# SchematicsEASYEDA.net
KiCad netlist of a schematic drawn in EasyEDA
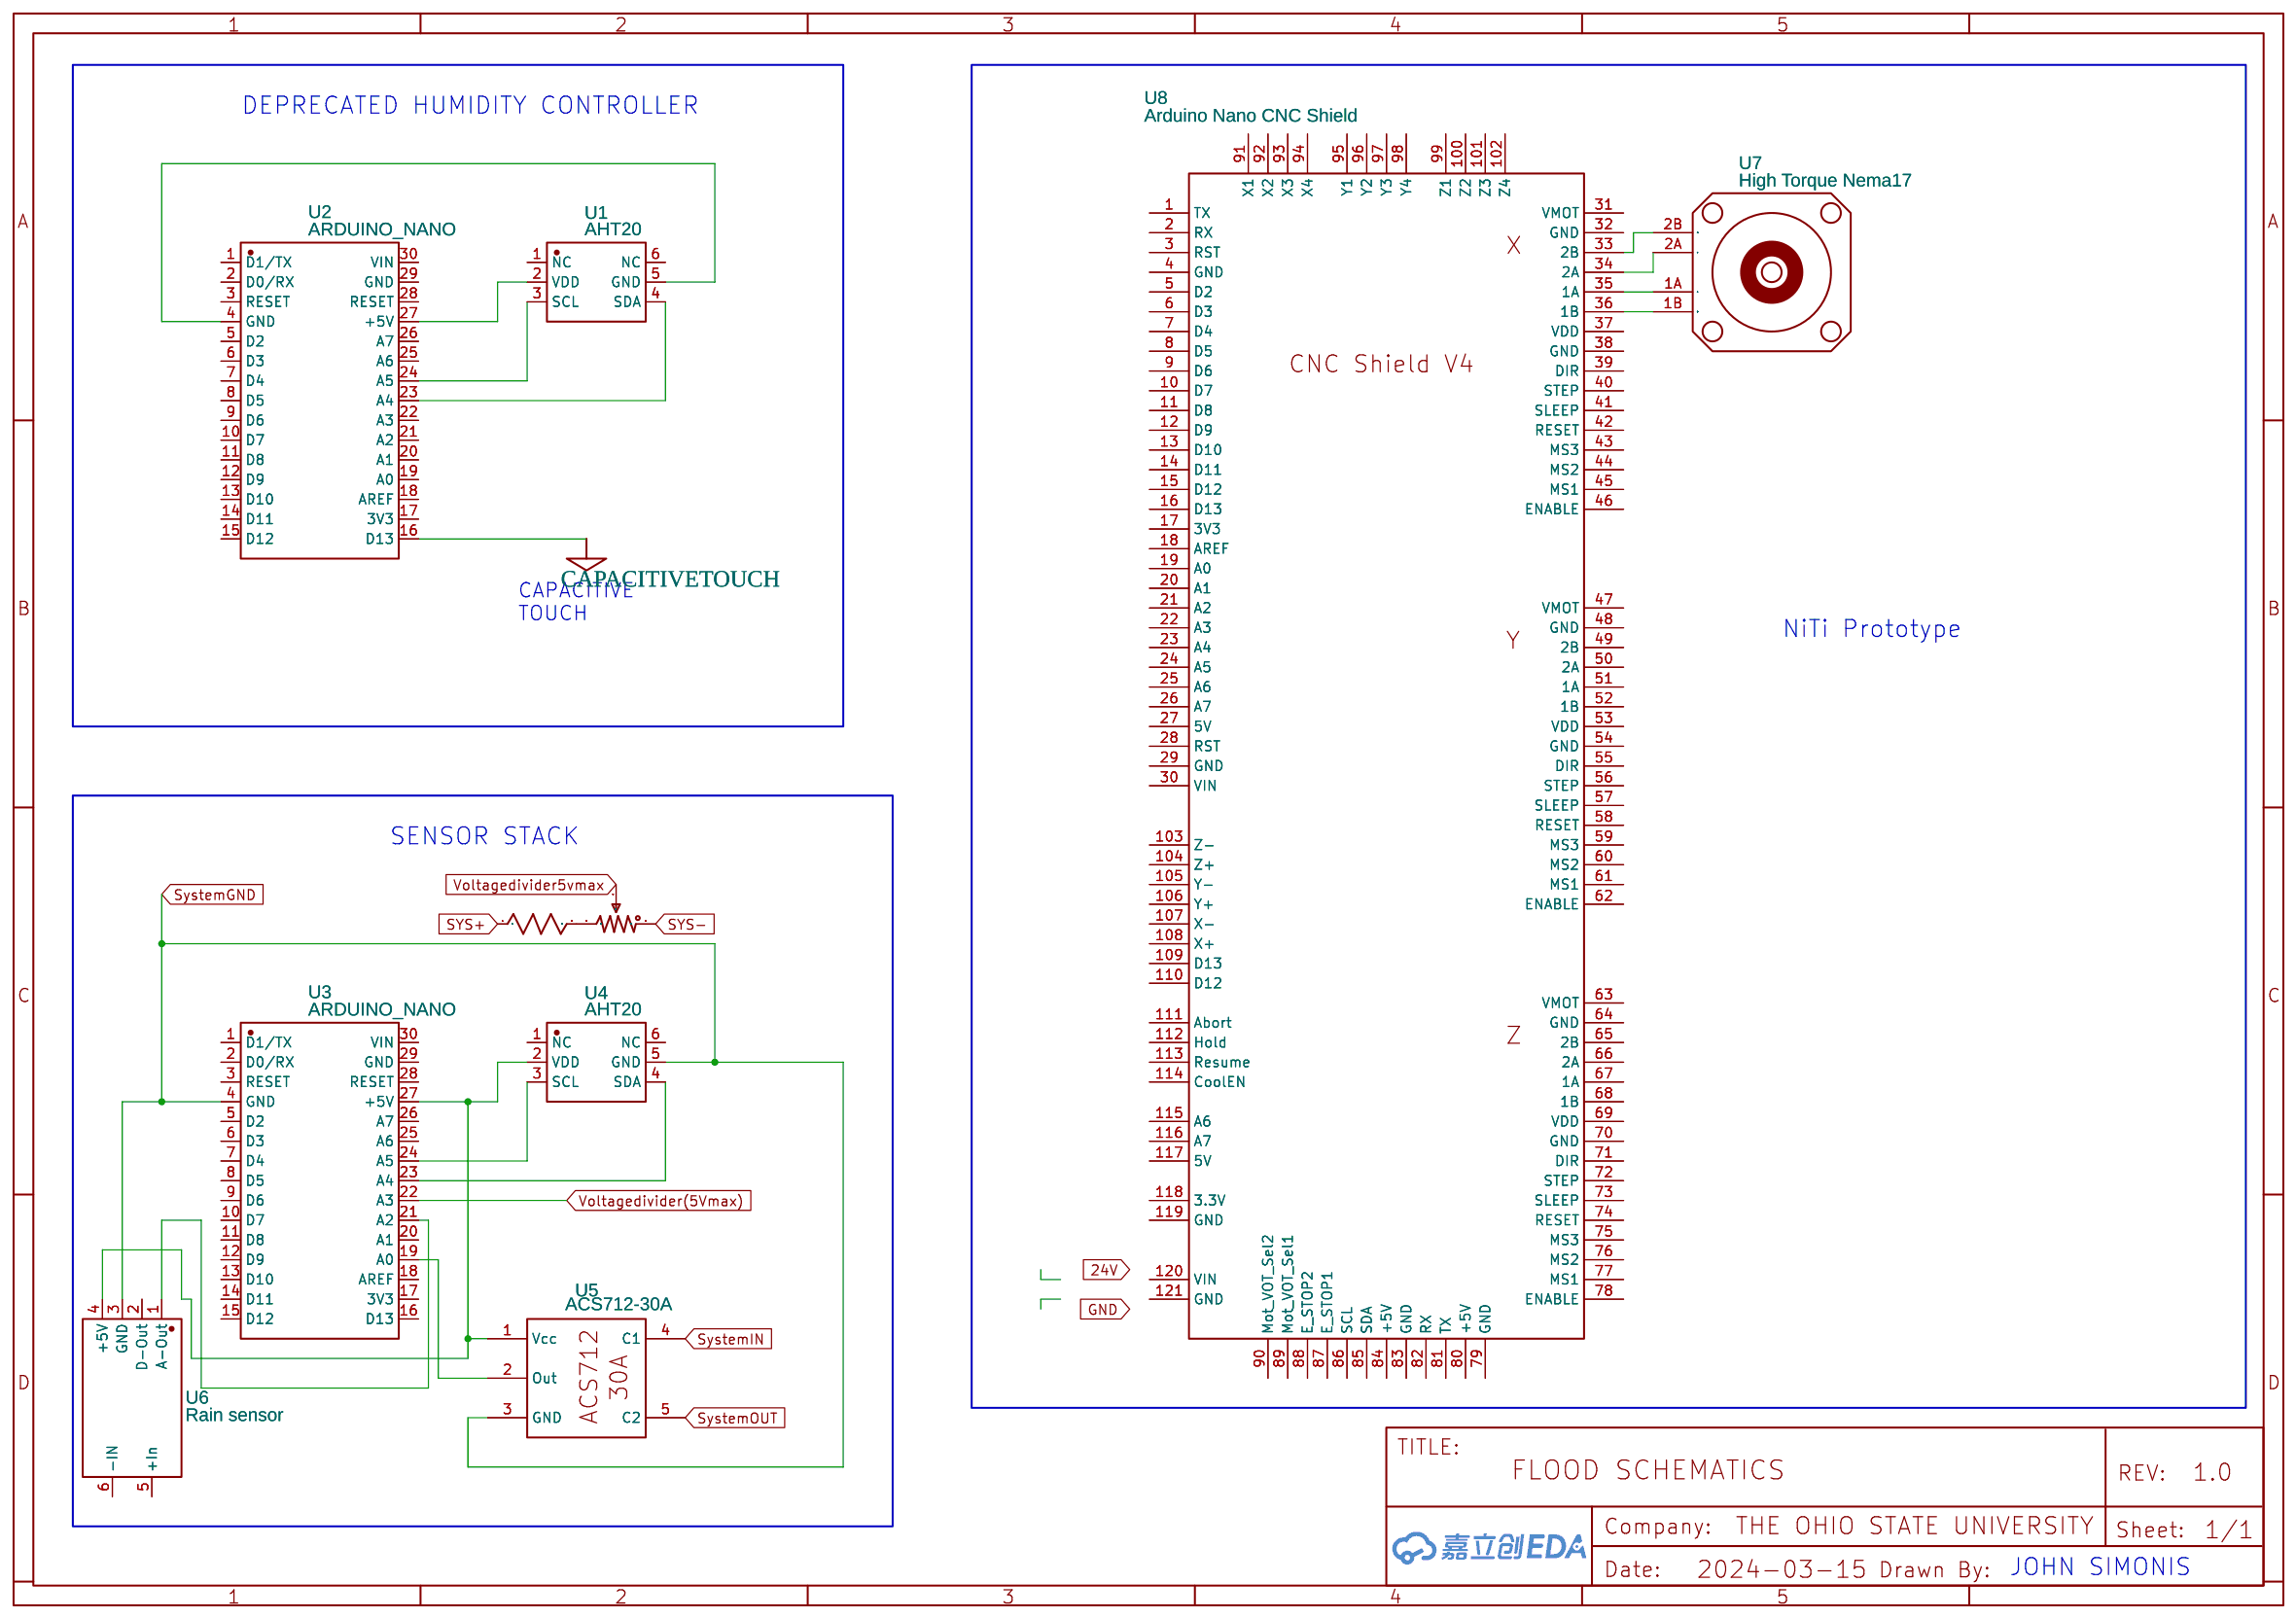
[diagram p0: schematic sheet]

(export (version "E")
  (design (tool "Eeschema 10.0.6"))
  (components
    (comp (ref "R1") (value "1k") (libsource (lib "") (part "R_0603_US")))
    (comp (ref "RP1") (value "R_3386P_US") (libsource (lib "") (part "R_3386P_US")))
    (comp (ref "U1")
      (value "AHT20")
      (fields (field (name "Manufacturer") "广州奥松"))
      (libsource (lib "") (part "AHT20"))
    )
    (comp (ref "U2") (value "ARDUINO_NANO") (libsource (lib "") (part "ARDUINO_NANO")))
    (comp (ref "U3") (value "ARDUINO_NANO") (libsource (lib "") (part "ARDUINO_NANO")))
    (comp (ref "U4")
      (value "AHT20")
      (fields (field (name "Manufacturer") "广州奥松"))
      (libsource (lib "") (part "AHT20"))
    )
    (comp (ref "U5") (value "ACS712-30A") (libsource (lib "") (part "ACS712-30A")))
    (comp (ref "U6") (value "Rain sensor") (libsource (lib "") (part "Rain sensor")))
    (comp (ref "U7") (value "High Torque Nema17") (libsource (lib "") (part "Nema17")))
    (comp (ref "U8") (value "Arduino Nano CNC Shield") (libsource (lib "") (part "Arduino Nano CNC Shield")))
  )
  (nets
    (net (code "2") (name "CAPACITIVETOUCH") (class "Default")
      (node (ref "U2") (pin "16") (pinfunction "D13_16") (pintype "unspecified"))
    )
    (net (code "4") (name "Net-(R1-Pad2)") (class "Default")
      (node (ref "R1") (pin "2") (pinfunction "2_2") (pintype "unspecified"))
      (node (ref "RP1") (pin "3") (pinfunction "3_3") (pintype "unspecified"))
    )
    (net (code "5") (name "Net-(U1-GND)") (class "Default")
      (node (ref "U1") (pin "5") (pinfunction "GND_5") (pintype "unspecified"))
      (node (ref "U2") (pin "4") (pinfunction "GND_4") (pintype "unspecified"))
    )
    (net (code "6") (name "Net-(U1-SCL)") (class "Default")
      (node (ref "U1") (pin "3") (pinfunction "SCL_3") (pintype "unspecified"))
      (node (ref "U2") (pin "24") (pinfunction "A5_24") (pintype "unspecified"))
    )
    (net (code "7") (name "Net-(U1-SDA)") (class "Default")
      (node (ref "U1") (pin "4") (pinfunction "SDA_4") (pintype "unspecified"))
      (node (ref "U2") (pin "23") (pinfunction "A4_23") (pintype "unspecified"))
    )
    (net (code "8") (name "Net-(U1-VDD)") (class "Default")
      (node (ref "U1") (pin "2") (pinfunction "VDD_2") (pintype "unspecified"))
      (node (ref "U2") (pin "27") (pinfunction "+5V_27") (pintype "unspecified"))
    )
    (net (code "9") (name "Net-(U3-+5V)") (class "Default")
      (node (ref "U3") (pin "27") (pinfunction "+5V_27") (pintype "unspecified"))
      (node (ref "U4") (pin "2") (pinfunction "VDD_2") (pintype "unspecified"))
      (node (ref "U5") (pin "1") (pinfunction "Vcc_1") (pintype "unspecified"))
      (node (ref "U6") (pin "4") (pinfunction "+5V_4") (pintype "unspecified"))
    )
    (net (code "10") (name "Net-(U3-A0)") (class "Default")
      (node (ref "U3") (pin "19") (pinfunction "A0_19") (pintype "unspecified"))
      (node (ref "U5") (pin "2") (pinfunction "Out_2") (pintype "unspecified"))
    )
    (net (code "11") (name "Net-(U3-A2)") (class "Default")
      (node (ref "U3") (pin "21") (pinfunction "A2_21") (pintype "unspecified"))
      (node (ref "U6") (pin "1") (pinfunction "A-Out_1") (pintype "unspecified"))
    )
    (net (code "12") (name "Net-(U3-A4)") (class "Default")
      (node (ref "U3") (pin "23") (pinfunction "A4_23") (pintype "unspecified"))
      (node (ref "U4") (pin "4") (pinfunction "SDA_4") (pintype "unspecified"))
    )
    (net (code "13") (name "Net-(U3-A5)") (class "Default")
      (node (ref "U3") (pin "24") (pinfunction "A5_24") (pintype "unspecified"))
      (node (ref "U4") (pin "3") (pinfunction "SCL_3") (pintype "unspecified"))
    )
    (net (code "14") (name "Net-(U7-A-Pad1A)") (class "Default")
      (node (ref "U7") (pin "1A") (pinfunction "A_1A") (pintype "unspecified"))
      (node (ref "U8") (pin "35") (pinfunction "1A_35") (pintype "unspecified"))
    )
    (net (code "15") (name "Net-(U7-A-Pad2A)") (class "Default")
      (node (ref "U7") (pin "2A") (pinfunction "A_2A") (pintype "unspecified"))
      (node (ref "U8") (pin "34") (pinfunction "2A_34") (pintype "unspecified"))
    )
    (net (code "16") (name "Net-(U7-B-Pad1B)") (class "Default")
      (node (ref "U7") (pin "1B") (pinfunction "B_1B") (pintype "unspecified"))
      (node (ref "U8") (pin "36") (pinfunction "1B_36") (pintype "unspecified"))
    )
    (net (code "17") (name "Net-(U7-B-Pad2B)") (class "Default")
      (node (ref "U7") (pin "2B") (pinfunction "B_2B") (pintype "unspecified"))
      (node (ref "U8") (pin "33") (pinfunction "2B_33") (pintype "unspecified"))
    )
    (net (code "18") (name "SYS+") (class "Default")
      (node (ref "R1") (pin "1") (pinfunction "1_1") (pintype "unspecified"))
    )
    (net (code "19") (name "SYS-") (class "Default")
      (node (ref "RP1") (pin "1") (pinfunction "1_1") (pintype "unspecified"))
    )
    (net (code "20") (name "SystemGND") (class "Default")
      (node (ref "U3") (pin "4") (pinfunction "GND_4") (pintype "unspecified"))
      (node (ref "U4") (pin "5") (pinfunction "GND_5") (pintype "unspecified"))
      (node (ref "U5") (pin "3") (pinfunction "GND_3") (pintype "unspecified"))
      (node (ref "U6") (pin "3") (pinfunction "GND_3") (pintype "unspecified"))
    )
    (net (code "21") (name "SystemIN") (class "Default")
      (node (ref "U5") (pin "4") (pinfunction "C1_4") (pintype "unspecified"))
    )
    (net (code "22") (name "SystemOUT") (class "Default")
      (node (ref "U5") (pin "5") (pinfunction "C2_5") (pintype "unspecified"))
    )
    (net (code "23") (name "Voltagedivider(5Vmax)") (class "Default")
      (node (ref "U3") (pin "22") (pinfunction "A3_22") (pintype "unspecified"))
    )
    (net (code "24") (name "Voltagedivider5vmax") (class "Default")
      (node (ref "RP1") (pin "2") (pinfunction "2_2") (pintype "unspecified"))
    )
    (net (code "25") (name "unconnected-(U1-NC-Pad1)") (class "Default")
      (node (ref "U1") (pin "1") (pinfunction "NC_1") (pintype "unspecified"))
    )
    (net (code "26") (name "unconnected-(U1-NC-Pad6)") (class "Default")
      (node (ref "U1") (pin "6") (pinfunction "NC_6") (pintype "unspecified"))
    )
    (net (code "27") (name "unconnected-(U2-3V3-Pad17)") (class "Default")
      (node (ref "U2") (pin "17") (pinfunction "3V3_17") (pintype "unspecified"))
    )
    (net (code "28") (name "unconnected-(U2-A0-Pad19)") (class "Default")
      (node (ref "U2") (pin "19") (pinfunction "A0_19") (pintype "unspecified"))
    )
    (net (code "29") (name "unconnected-(U2-A1-Pad20)") (class "Default")
      (node (ref "U2") (pin "20") (pinfunction "A1_20") (pintype "unspecified"))
    )
    (net (code "30") (name "unconnected-(U2-A2-Pad21)") (class "Default")
      (node (ref "U2") (pin "21") (pinfunction "A2_21") (pintype "unspecified"))
    )
    (net (code "31") (name "unconnected-(U2-A3-Pad22)") (class "Default")
      (node (ref "U2") (pin "22") (pinfunction "A3_22") (pintype "unspecified"))
    )
    (net (code "32") (name "unconnected-(U2-A6-Pad25)") (class "Default")
      (node (ref "U2") (pin "25") (pinfunction "A6_25") (pintype "unspecified"))
    )
    (net (code "33") (name "unconnected-(U2-A7-Pad26)") (class "Default")
      (node (ref "U2") (pin "26") (pinfunction "A7_26") (pintype "unspecified"))
    )
    (net (code "34") (name "unconnected-(U2-AREF-Pad18)") (class "Default")
      (node (ref "U2") (pin "18") (pinfunction "AREF_18") (pintype "unspecified"))
    )
    (net (code "35") (name "unconnected-(U2-D0{slash}RX-Pad2)") (class "Default")
      (node (ref "U2") (pin "2") (pinfunction "D0/RX_2") (pintype "unspecified"))
    )
    (net (code "36") (name "unconnected-(U2-D1{slash}TX-Pad1)") (class "Default")
      (node (ref "U2") (pin "1") (pinfunction "D1/TX_1") (pintype "unspecified"))
    )
    (net (code "37") (name "unconnected-(U2-D2-Pad5)") (class "Default")
      (node (ref "U2") (pin "5") (pinfunction "D2_5") (pintype "unspecified"))
    )
    (net (code "38") (name "unconnected-(U2-D3-Pad6)") (class "Default")
      (node (ref "U2") (pin "6") (pinfunction "D3_6") (pintype "unspecified"))
    )
    (net (code "39") (name "unconnected-(U2-D4-Pad7)") (class "Default")
      (node (ref "U2") (pin "7") (pinfunction "D4_7") (pintype "unspecified"))
    )
    (net (code "40") (name "unconnected-(U2-D5-Pad8)") (class "Default")
      (node (ref "U2") (pin "8") (pinfunction "D5_8") (pintype "unspecified"))
    )
    (net (code "41") (name "unconnected-(U2-D6-Pad9)") (class "Default")
      (node (ref "U2") (pin "9") (pinfunction "D6_9") (pintype "unspecified"))
    )
    (net (code "42") (name "unconnected-(U2-D7-Pad10)") (class "Default")
      (node (ref "U2") (pin "10") (pinfunction "D7_10") (pintype "unspecified"))
    )
    (net (code "43") (name "unconnected-(U2-D8-Pad11)") (class "Default")
      (node (ref "U2") (pin "11") (pinfunction "D8_11") (pintype "unspecified"))
    )
    (net (code "44") (name "unconnected-(U2-D9-Pad12)") (class "Default")
      (node (ref "U2") (pin "12") (pinfunction "D9_12") (pintype "unspecified"))
    )
    (net (code "45") (name "unconnected-(U2-D10-Pad13)") (class "Default")
      (node (ref "U2") (pin "13") (pinfunction "D10_13") (pintype "unspecified"))
    )
    (net (code "46") (name "unconnected-(U2-D11-Pad14)") (class "Default")
      (node (ref "U2") (pin "14") (pinfunction "D11_14") (pintype "unspecified"))
    )
    (net (code "47") (name "unconnected-(U2-D12-Pad15)") (class "Default")
      (node (ref "U2") (pin "15") (pinfunction "D12_15") (pintype "unspecified"))
    )
    (net (code "48") (name "unconnected-(U2-GND-Pad29)") (class "Default")
      (node (ref "U2") (pin "29") (pinfunction "GND_29") (pintype "unspecified"))
    )
    (net (code "49") (name "unconnected-(U2-RESET-Pad3)") (class "Default")
      (node (ref "U2") (pin "3") (pinfunction "RESET_3") (pintype "unspecified"))
    )
    (net (code "50") (name "unconnected-(U2-RESET-Pad28)") (class "Default")
      (node (ref "U2") (pin "28") (pinfunction "RESET_28") (pintype "unspecified"))
    )
    (net (code "51") (name "unconnected-(U2-VIN-Pad30)") (class "Default")
      (node (ref "U2") (pin "30") (pinfunction "VIN_30") (pintype "unspecified"))
    )
    (net (code "52") (name "unconnected-(U3-3V3-Pad17)") (class "Default")
      (node (ref "U3") (pin "17") (pinfunction "3V3_17") (pintype "unspecified"))
    )
    (net (code "53") (name "unconnected-(U3-A1-Pad20)") (class "Default")
      (node (ref "U3") (pin "20") (pinfunction "A1_20") (pintype "unspecified"))
    )
    (net (code "54") (name "unconnected-(U3-A6-Pad25)") (class "Default")
      (node (ref "U3") (pin "25") (pinfunction "A6_25") (pintype "unspecified"))
    )
    (net (code "55") (name "unconnected-(U3-A7-Pad26)") (class "Default")
      (node (ref "U3") (pin "26") (pinfunction "A7_26") (pintype "unspecified"))
    )
    (net (code "56") (name "unconnected-(U3-AREF-Pad18)") (class "Default")
      (node (ref "U3") (pin "18") (pinfunction "AREF_18") (pintype "unspecified"))
    )
    (net (code "57") (name "unconnected-(U3-D0{slash}RX-Pad2)") (class "Default")
      (node (ref "U3") (pin "2") (pinfunction "D0/RX_2") (pintype "unspecified"))
    )
    (net (code "58") (name "unconnected-(U3-D1{slash}TX-Pad1)") (class "Default")
      (node (ref "U3") (pin "1") (pinfunction "D1/TX_1") (pintype "unspecified"))
    )
    (net (code "59") (name "unconnected-(U3-D2-Pad5)") (class "Default")
      (node (ref "U3") (pin "5") (pinfunction "D2_5") (pintype "unspecified"))
    )
    (net (code "60") (name "unconnected-(U3-D3-Pad6)") (class "Default")
      (node (ref "U3") (pin "6") (pinfunction "D3_6") (pintype "unspecified"))
    )
    (net (code "61") (name "unconnected-(U3-D4-Pad7)") (class "Default")
      (node (ref "U3") (pin "7") (pinfunction "D4_7") (pintype "unspecified"))
    )
    (net (code "62") (name "unconnected-(U3-D5-Pad8)") (class "Default")
      (node (ref "U3") (pin "8") (pinfunction "D5_8") (pintype "unspecified"))
    )
    (net (code "63") (name "unconnected-(U3-D6-Pad9)") (class "Default")
      (node (ref "U3") (pin "9") (pinfunction "D6_9") (pintype "unspecified"))
    )
    (net (code "64") (name "unconnected-(U3-D7-Pad10)") (class "Default")
      (node (ref "U3") (pin "10") (pinfunction "D7_10") (pintype "unspecified"))
    )
    (net (code "65") (name "unconnected-(U3-D8-Pad11)") (class "Default")
      (node (ref "U3") (pin "11") (pinfunction "D8_11") (pintype "unspecified"))
    )
    (net (code "66") (name "unconnected-(U3-D9-Pad12)") (class "Default")
      (node (ref "U3") (pin "12") (pinfunction "D9_12") (pintype "unspecified"))
    )
    (net (code "67") (name "unconnected-(U3-D10-Pad13)") (class "Default")
      (node (ref "U3") (pin "13") (pinfunction "D10_13") (pintype "unspecified"))
    )
    (net (code "68") (name "unconnected-(U3-D11-Pad14)") (class "Default")
      (node (ref "U3") (pin "14") (pinfunction "D11_14") (pintype "unspecified"))
    )
    (net (code "69") (name "unconnected-(U3-D12-Pad15)") (class "Default")
      (node (ref "U3") (pin "15") (pinfunction "D12_15") (pintype "unspecified"))
    )
    (net (code "70") (name "unconnected-(U3-D13-Pad16)") (class "Default")
      (node (ref "U3") (pin "16") (pinfunction "D13_16") (pintype "unspecified"))
    )
    (net (code "71") (name "unconnected-(U3-GND-Pad29)") (class "Default")
      (node (ref "U3") (pin "29") (pinfunction "GND_29") (pintype "unspecified"))
    )
    (net (code "72") (name "unconnected-(U3-RESET-Pad3)") (class "Default")
      (node (ref "U3") (pin "3") (pinfunction "RESET_3") (pintype "unspecified"))
    )
    (net (code "73") (name "unconnected-(U3-RESET-Pad28)") (class "Default")
      (node (ref "U3") (pin "28") (pinfunction "RESET_28") (pintype "unspecified"))
    )
    (net (code "74") (name "unconnected-(U3-VIN-Pad30)") (class "Default")
      (node (ref "U3") (pin "30") (pinfunction "VIN_30") (pintype "unspecified"))
    )
    (net (code "75") (name "unconnected-(U4-NC-Pad1)") (class "Default")
      (node (ref "U4") (pin "1") (pinfunction "NC_1") (pintype "unspecified"))
    )
    (net (code "76") (name "unconnected-(U4-NC-Pad6)") (class "Default")
      (node (ref "U4") (pin "6") (pinfunction "NC_6") (pintype "unspecified"))
    )
    (net (code "77") (name "unconnected-(U6-+In-Pad5)") (class "Default")
      (node (ref "U6") (pin "5") (pinfunction "+In_5") (pintype "unspecified"))
    )
    (net (code "78") (name "unconnected-(U6--IN-Pad6)") (class "Default")
      (node (ref "U6") (pin "6") (pinfunction "-IN_6") (pintype "unspecified"))
    )
    (net (code "79") (name "unconnected-(U6-D-Out-Pad2)") (class "Default")
      (node (ref "U6") (pin "2") (pinfunction "D-Out_2") (pintype "unspecified"))
    )
    (net (code "80") (name "unconnected-(U8-+5V-Pad80)") (class "Default")
      (node (ref "U8") (pin "80") (pinfunction "+5V_80") (pintype "unspecified"))
    )
    (net (code "81") (name "unconnected-(U8-+5V-Pad84)") (class "Default")
      (node (ref "U8") (pin "84") (pinfunction "+5V_84") (pintype "unspecified"))
    )
    (net (code "82") (name "unconnected-(U8-1A-Pad51)") (class "Default")
      (node (ref "U8") (pin "51") (pinfunction "1A_51") (pintype "unspecified"))
    )
    (net (code "83") (name "unconnected-(U8-1A-Pad67)") (class "Default")
      (node (ref "U8") (pin "67") (pinfunction "1A_67") (pintype "unspecified"))
    )
    (net (code "84") (name "unconnected-(U8-1B-Pad52)") (class "Default")
      (node (ref "U8") (pin "52") (pinfunction "1B_52") (pintype "unspecified"))
    )
    (net (code "85") (name "unconnected-(U8-1B-Pad68)") (class "Default")
      (node (ref "U8") (pin "68") (pinfunction "1B_68") (pintype "unspecified"))
    )
    (net (code "86") (name "unconnected-(U8-2A-Pad50)") (class "Default")
      (node (ref "U8") (pin "50") (pinfunction "2A_50") (pintype "unspecified"))
    )
    (net (code "87") (name "unconnected-(U8-2A-Pad66)") (class "Default")
      (node (ref "U8") (pin "66") (pinfunction "2A_66") (pintype "unspecified"))
    )
    (net (code "88") (name "unconnected-(U8-2B-Pad49)") (class "Default")
      (node (ref "U8") (pin "49") (pinfunction "2B_49") (pintype "unspecified"))
    )
    (net (code "89") (name "unconnected-(U8-2B-Pad65)") (class "Default")
      (node (ref "U8") (pin "65") (pinfunction "2B_65") (pintype "unspecified"))
    )
    (net (code "90") (name "unconnected-(U8-3.3V-Pad118)") (class "Default")
      (node (ref "U8") (pin "118") (pinfunction "3.3V_118") (pintype "unspecified"))
    )
    (net (code "91") (name "unconnected-(U8-3V3-Pad17)") (class "Default")
      (node (ref "U8") (pin "17") (pinfunction "3V3_17") (pintype "unspecified"))
    )
    (net (code "92") (name "unconnected-(U8-5V-Pad27)") (class "Default")
      (node (ref "U8") (pin "27") (pinfunction "5V_27") (pintype "unspecified"))
    )
    (net (code "93") (name "unconnected-(U8-5V-Pad117)") (class "Default")
      (node (ref "U8") (pin "117") (pinfunction "5V_117") (pintype "unspecified"))
    )
    (net (code "94") (name "unconnected-(U8-A0-Pad19)") (class "Default")
      (node (ref "U8") (pin "19") (pinfunction "A0_19") (pintype "unspecified"))
    )
    (net (code "95") (name "unconnected-(U8-A1-Pad20)") (class "Default")
      (node (ref "U8") (pin "20") (pinfunction "A1_20") (pintype "unspecified"))
    )
    (net (code "96") (name "unconnected-(U8-A2-Pad21)") (class "Default")
      (node (ref "U8") (pin "21") (pinfunction "A2_21") (pintype "unspecified"))
    )
    (net (code "97") (name "unconnected-(U8-A3-Pad22)") (class "Default")
      (node (ref "U8") (pin "22") (pinfunction "A3_22") (pintype "unspecified"))
    )
    (net (code "98") (name "unconnected-(U8-A4-Pad23)") (class "Default")
      (node (ref "U8") (pin "23") (pinfunction "A4_23") (pintype "unspecified"))
    )
    (net (code "99") (name "unconnected-(U8-A5-Pad24)") (class "Default")
      (node (ref "U8") (pin "24") (pinfunction "A5_24") (pintype "unspecified"))
    )
    (net (code "100") (name "unconnected-(U8-A6-Pad25)") (class "Default")
      (node (ref "U8") (pin "25") (pinfunction "A6_25") (pintype "unspecified"))
    )
    (net (code "101") (name "unconnected-(U8-A6-Pad115)") (class "Default")
      (node (ref "U8") (pin "115") (pinfunction "A6_115") (pintype "unspecified"))
    )
    (net (code "102") (name "unconnected-(U8-A7-Pad26)") (class "Default")
      (node (ref "U8") (pin "26") (pinfunction "A7_26") (pintype "unspecified"))
    )
    (net (code "103") (name "unconnected-(U8-A7-Pad116)") (class "Default")
      (node (ref "U8") (pin "116") (pinfunction "A7_116") (pintype "unspecified"))
    )
    (net (code "104") (name "unconnected-(U8-AREF-Pad18)") (class "Default")
      (node (ref "U8") (pin "18") (pinfunction "AREF_18") (pintype "unspecified"))
    )
    (net (code "105") (name "unconnected-(U8-Abort-Pad111)") (class "Default")
      (node (ref "U8") (pin "111") (pinfunction "Abort_111") (pintype "unspecified"))
    )
    (net (code "106") (name "unconnected-(U8-CoolEN-Pad114)") (class "Default")
      (node (ref "U8") (pin "114") (pinfunction "CoolEN_114") (pintype "unspecified"))
    )
    (net (code "107") (name "unconnected-(U8-D2-Pad5)") (class "Default")
      (node (ref "U8") (pin "5") (pinfunction "D2_5") (pintype "unspecified"))
    )
    (net (code "108") (name "unconnected-(U8-D3-Pad6)") (class "Default")
      (node (ref "U8") (pin "6") (pinfunction "D3_6") (pintype "unspecified"))
    )
    (net (code "109") (name "unconnected-(U8-D4-Pad7)") (class "Default")
      (node (ref "U8") (pin "7") (pinfunction "D4_7") (pintype "unspecified"))
    )
    (net (code "110") (name "unconnected-(U8-D5-Pad8)") (class "Default")
      (node (ref "U8") (pin "8") (pinfunction "D5_8") (pintype "unspecified"))
    )
    (net (code "111") (name "unconnected-(U8-D6-Pad9)") (class "Default")
      (node (ref "U8") (pin "9") (pinfunction "D6_9") (pintype "unspecified"))
    )
    (net (code "112") (name "unconnected-(U8-D7-Pad10)") (class "Default")
      (node (ref "U8") (pin "10") (pinfunction "D7_10") (pintype "unspecified"))
    )
    (net (code "113") (name "unconnected-(U8-D8-Pad11)") (class "Default")
      (node (ref "U8") (pin "11") (pinfunction "D8_11") (pintype "unspecified"))
    )
    (net (code "114") (name "unconnected-(U8-D9-Pad12)") (class "Default")
      (node (ref "U8") (pin "12") (pinfunction "D9_12") (pintype "unspecified"))
    )
    (net (code "115") (name "unconnected-(U8-D10-Pad13)") (class "Default")
      (node (ref "U8") (pin "13") (pinfunction "D10_13") (pintype "unspecified"))
    )
    (net (code "116") (name "unconnected-(U8-D11-Pad14)") (class "Default")
      (node (ref "U8") (pin "14") (pinfunction "D11_14") (pintype "unspecified"))
    )
    (net (code "117") (name "unconnected-(U8-D12-Pad15)") (class "Default")
      (node (ref "U8") (pin "15") (pinfunction "D12_15") (pintype "unspecified"))
    )
    (net (code "118") (name "unconnected-(U8-D12-Pad110)") (class "Default")
      (node (ref "U8") (pin "110") (pinfunction "D12_110") (pintype "unspecified"))
    )
    (net (code "119") (name "unconnected-(U8-D13-Pad16)") (class "Default")
      (node (ref "U8") (pin "16") (pinfunction "D13_16") (pintype "unspecified"))
    )
    (net (code "120") (name "unconnected-(U8-D13-Pad109)") (class "Default")
      (node (ref "U8") (pin "109") (pinfunction "D13_109") (pintype "unspecified"))
    )
    (net (code "121") (name "unconnected-(U8-DIR-Pad39)") (class "Default")
      (node (ref "U8") (pin "39") (pinfunction "DIR_39") (pintype "unspecified"))
    )
    (net (code "122") (name "unconnected-(U8-DIR-Pad55)") (class "Default")
      (node (ref "U8") (pin "55") (pinfunction "DIR_55") (pintype "unspecified"))
    )
    (net (code "123") (name "unconnected-(U8-DIR-Pad71)") (class "Default")
      (node (ref "U8") (pin "71") (pinfunction "DIR_71") (pintype "unspecified"))
    )
    (net (code "124") (name "unconnected-(U8-ENABLE-Pad46)") (class "Default")
      (node (ref "U8") (pin "46") (pinfunction "ENABLE_46") (pintype "unspecified"))
    )
    (net (code "125") (name "unconnected-(U8-ENABLE-Pad62)") (class "Default")
      (node (ref "U8") (pin "62") (pinfunction "ENABLE_62") (pintype "unspecified"))
    )
    (net (code "126") (name "unconnected-(U8-ENABLE-Pad78)") (class "Default")
      (node (ref "U8") (pin "78") (pinfunction "ENABLE_78") (pintype "unspecified"))
    )
    (net (code "127") (name "unconnected-(U8-E_STOP1-Pad87)") (class "Default")
      (node (ref "U8") (pin "87") (pinfunction "E_STOP1_87") (pintype "unspecified"))
    )
    (net (code "128") (name "unconnected-(U8-E_STOP2-Pad88)") (class "Default")
      (node (ref "U8") (pin "88") (pinfunction "E_STOP2_88") (pintype "unspecified"))
    )
    (net (code "129") (name "unconnected-(U8-GND-Pad4)") (class "Default")
      (node (ref "U8") (pin "4") (pinfunction "GND_4") (pintype "unspecified"))
    )
    (net (code "130") (name "unconnected-(U8-GND-Pad29)") (class "Default")
      (node (ref "U8") (pin "29") (pinfunction "GND_29") (pintype "unspecified"))
    )
    (net (code "131") (name "unconnected-(U8-GND-Pad32)") (class "Default")
      (node (ref "U8") (pin "32") (pinfunction "GND_32") (pintype "unspecified"))
    )
    (net (code "132") (name "unconnected-(U8-GND-Pad38)") (class "Default")
      (node (ref "U8") (pin "38") (pinfunction "GND_38") (pintype "unspecified"))
    )
    (net (code "133") (name "unconnected-(U8-GND-Pad48)") (class "Default")
      (node (ref "U8") (pin "48") (pinfunction "GND_48") (pintype "unspecified"))
    )
    (net (code "134") (name "unconnected-(U8-GND-Pad54)") (class "Default")
      (node (ref "U8") (pin "54") (pinfunction "GND_54") (pintype "unspecified"))
    )
    (net (code "135") (name "unconnected-(U8-GND-Pad64)") (class "Default")
      (node (ref "U8") (pin "64") (pinfunction "GND_64") (pintype "unspecified"))
    )
    (net (code "136") (name "unconnected-(U8-GND-Pad70)") (class "Default")
      (node (ref "U8") (pin "70") (pinfunction "GND_70") (pintype "unspecified"))
    )
    (net (code "137") (name "unconnected-(U8-GND-Pad79)") (class "Default")
      (node (ref "U8") (pin "79") (pinfunction "GND_79") (pintype "unspecified"))
    )
    (net (code "138") (name "unconnected-(U8-GND-Pad83)") (class "Default")
      (node (ref "U8") (pin "83") (pinfunction "GND_83") (pintype "unspecified"))
    )
    (net (code "139") (name "unconnected-(U8-GND-Pad119)") (class "Default")
      (node (ref "U8") (pin "119") (pinfunction "GND_119") (pintype "unspecified"))
    )
    (net (code "140") (name "unconnected-(U8-GND-Pad121)") (class "Default")
      (node (ref "U8") (pin "121") (pinfunction "GND_121") (pintype "unspecified"))
    )
    (net (code "141") (name "unconnected-(U8-Hold-Pad112)") (class "Default")
      (node (ref "U8") (pin "112") (pinfunction "Hold_112") (pintype "unspecified"))
    )
    (net (code "142") (name "unconnected-(U8-MS1-Pad45)") (class "Default")
      (node (ref "U8") (pin "45") (pinfunction "MS1_45") (pintype "unspecified"))
    )
    (net (code "143") (name "unconnected-(U8-MS1-Pad61)") (class "Default")
      (node (ref "U8") (pin "61") (pinfunction "MS1_61") (pintype "unspecified"))
    )
    (net (code "144") (name "unconnected-(U8-MS1-Pad77)") (class "Default")
      (node (ref "U8") (pin "77") (pinfunction "MS1_77") (pintype "unspecified"))
    )
    (net (code "145") (name "unconnected-(U8-MS2-Pad44)") (class "Default")
      (node (ref "U8") (pin "44") (pinfunction "MS2_44") (pintype "unspecified"))
    )
    (net (code "146") (name "unconnected-(U8-MS2-Pad60)") (class "Default")
      (node (ref "U8") (pin "60") (pinfunction "MS2_60") (pintype "unspecified"))
    )
    (net (code "147") (name "unconnected-(U8-MS2-Pad76)") (class "Default")
      (node (ref "U8") (pin "76") (pinfunction "MS2_76") (pintype "unspecified"))
    )
    (net (code "148") (name "unconnected-(U8-MS3-Pad43)") (class "Default")
      (node (ref "U8") (pin "43") (pinfunction "MS3_43") (pintype "unspecified"))
    )
    (net (code "149") (name "unconnected-(U8-MS3-Pad59)") (class "Default")
      (node (ref "U8") (pin "59") (pinfunction "MS3_59") (pintype "unspecified"))
    )
    (net (code "150") (name "unconnected-(U8-MS3-Pad75)") (class "Default")
      (node (ref "U8") (pin "75") (pinfunction "MS3_75") (pintype "unspecified"))
    )
    (net (code "151") (name "unconnected-(U8-Mot_VOT_Sel1-Pad89)") (class "Default")
      (node (ref "U8") (pin "89") (pinfunction "Mot_VOT_Sel1_89") (pintype "unspecified"))
    )
    (net (code "152") (name "unconnected-(U8-Mot_VOT_Sel2-Pad90)") (class "Default")
      (node (ref "U8") (pin "90") (pinfunction "Mot_VOT_Sel2_90") (pintype "unspecified"))
    )
    (net (code "153") (name "unconnected-(U8-RESET-Pad42)") (class "Default")
      (node (ref "U8") (pin "42") (pinfunction "RESET_42") (pintype "unspecified"))
    )
    (net (code "154") (name "unconnected-(U8-RESET-Pad58)") (class "Default")
      (node (ref "U8") (pin "58") (pinfunction "RESET_58") (pintype "unspecified"))
    )
    (net (code "155") (name "unconnected-(U8-RESET-Pad74)") (class "Default")
      (node (ref "U8") (pin "74") (pinfunction "RESET_74") (pintype "unspecified"))
    )
    (net (code "156") (name "unconnected-(U8-RST-Pad3)") (class "Default")
      (node (ref "U8") (pin "3") (pinfunction "RST_3") (pintype "unspecified"))
    )
    (net (code "157") (name "unconnected-(U8-RST-Pad28)") (class "Default")
      (node (ref "U8") (pin "28") (pinfunction "RST_28") (pintype "unspecified"))
    )
    (net (code "158") (name "unconnected-(U8-RX-Pad2)") (class "Default")
      (node (ref "U8") (pin "2") (pinfunction "RX_2") (pintype "unspecified"))
    )
    (net (code "159") (name "unconnected-(U8-RX-Pad82)") (class "Default")
      (node (ref "U8") (pin "82") (pinfunction "RX_82") (pintype "unspecified"))
    )
    (net (code "160") (name "unconnected-(U8-Resume-Pad113)") (class "Default")
      (node (ref "U8") (pin "113") (pinfunction "Resume_113") (pintype "unspecified"))
    )
    (net (code "161") (name "unconnected-(U8-SCL-Pad86)") (class "Default")
      (node (ref "U8") (pin "86") (pinfunction "SCL_86") (pintype "unspecified"))
    )
    (net (code "162") (name "unconnected-(U8-SDA-Pad85)") (class "Default")
      (node (ref "U8") (pin "85") (pinfunction "SDA_85") (pintype "unspecified"))
    )
    (net (code "163") (name "unconnected-(U8-SLEEP-Pad41)") (class "Default")
      (node (ref "U8") (pin "41") (pinfunction "SLEEP_41") (pintype "unspecified"))
    )
    (net (code "164") (name "unconnected-(U8-SLEEP-Pad57)") (class "Default")
      (node (ref "U8") (pin "57") (pinfunction "SLEEP_57") (pintype "unspecified"))
    )
    (net (code "165") (name "unconnected-(U8-SLEEP-Pad73)") (class "Default")
      (node (ref "U8") (pin "73") (pinfunction "SLEEP_73") (pintype "unspecified"))
    )
    (net (code "166") (name "unconnected-(U8-STEP-Pad40)") (class "Default")
      (node (ref "U8") (pin "40") (pinfunction "STEP_40") (pintype "unspecified"))
    )
    (net (code "167") (name "unconnected-(U8-STEP-Pad56)") (class "Default")
      (node (ref "U8") (pin "56") (pinfunction "STEP_56") (pintype "unspecified"))
    )
    (net (code "168") (name "unconnected-(U8-STEP-Pad72)") (class "Default")
      (node (ref "U8") (pin "72") (pinfunction "STEP_72") (pintype "unspecified"))
    )
    (net (code "169") (name "unconnected-(U8-TX-Pad1)") (class "Default")
      (node (ref "U8") (pin "1") (pinfunction "TX_1") (pintype "unspecified"))
    )
    (net (code "170") (name "unconnected-(U8-TX-Pad81)") (class "Default")
      (node (ref "U8") (pin "81") (pinfunction "TX_81") (pintype "unspecified"))
    )
    (net (code "171") (name "unconnected-(U8-VDD-Pad37)") (class "Default")
      (node (ref "U8") (pin "37") (pinfunction "VDD_37") (pintype "unspecified"))
    )
    (net (code "172") (name "unconnected-(U8-VDD-Pad53)") (class "Default")
      (node (ref "U8") (pin "53") (pinfunction "VDD_53") (pintype "unspecified"))
    )
    (net (code "173") (name "unconnected-(U8-VDD-Pad69)") (class "Default")
      (node (ref "U8") (pin "69") (pinfunction "VDD_69") (pintype "unspecified"))
    )
    (net (code "174") (name "unconnected-(U8-VIN-Pad30)") (class "Default")
      (node (ref "U8") (pin "30") (pinfunction "VIN_30") (pintype "unspecified"))
    )
    (net (code "175") (name "unconnected-(U8-VIN-Pad120)") (class "Default")
      (node (ref "U8") (pin "120") (pinfunction "VIN_120") (pintype "unspecified"))
    )
    (net (code "176") (name "unconnected-(U8-VMOT-Pad31)") (class "Default")
      (node (ref "U8") (pin "31") (pinfunction "VMOT_31") (pintype "unspecified"))
    )
    (net (code "177") (name "unconnected-(U8-VMOT-Pad47)") (class "Default")
      (node (ref "U8") (pin "47") (pinfunction "VMOT_47") (pintype "unspecified"))
    )
    (net (code "178") (name "unconnected-(U8-VMOT-Pad63)") (class "Default")
      (node (ref "U8") (pin "63") (pinfunction "VMOT_63") (pintype "unspecified"))
    )
    (net (code "179") (name "unconnected-(U8-X+-Pad108)") (class "Default")
      (node (ref "U8") (pin "108") (pinfunction "X+_108") (pintype "unspecified"))
    )
    (net (code "180") (name "unconnected-(U8-X--Pad107)") (class "Default")
      (node (ref "U8") (pin "107") (pinfunction "X-_107") (pintype "unspecified"))
    )
    (net (code "181") (name "unconnected-(U8-X1-Pad91)") (class "Default")
      (node (ref "U8") (pin "91") (pinfunction "X1_91") (pintype "unspecified"))
    )
    (net (code "182") (name "unconnected-(U8-X2-Pad92)") (class "Default")
      (node (ref "U8") (pin "92") (pinfunction "X2_92") (pintype "unspecified"))
    )
    (net (code "183") (name "unconnected-(U8-X3-Pad93)") (class "Default")
      (node (ref "U8") (pin "93") (pinfunction "X3_93") (pintype "unspecified"))
    )
    (net (code "184") (name "unconnected-(U8-X4-Pad94)") (class "Default")
      (node (ref "U8") (pin "94") (pinfunction "X4_94") (pintype "unspecified"))
    )
    (net (code "185") (name "unconnected-(U8-Y+-Pad106)") (class "Default")
      (node (ref "U8") (pin "106") (pinfunction "Y+_106") (pintype "unspecified"))
    )
    (net (code "186") (name "unconnected-(U8-Y--Pad105)") (class "Default")
      (node (ref "U8") (pin "105") (pinfunction "Y-_105") (pintype "unspecified"))
    )
    (net (code "187") (name "unconnected-(U8-Y1-Pad95)") (class "Default")
      (node (ref "U8") (pin "95") (pinfunction "Y1_95") (pintype "unspecified"))
    )
    (net (code "188") (name "unconnected-(U8-Y2-Pad96)") (class "Default")
      (node (ref "U8") (pin "96") (pinfunction "Y2_96") (pintype "unspecified"))
    )
    (net (code "189") (name "unconnected-(U8-Y3-Pad97)") (class "Default")
      (node (ref "U8") (pin "97") (pinfunction "Y3_97") (pintype "unspecified"))
    )
    (net (code "190") (name "unconnected-(U8-Y4-Pad98)") (class "Default")
      (node (ref "U8") (pin "98") (pinfunction "Y4_98") (pintype "unspecified"))
    )
    (net (code "191") (name "unconnected-(U8-Z+-Pad104)") (class "Default")
      (node (ref "U8") (pin "104") (pinfunction "Z+_104") (pintype "unspecified"))
    )
    (net (code "192") (name "unconnected-(U8-Z--Pad103)") (class "Default")
      (node (ref "U8") (pin "103") (pinfunction "Z-_103") (pintype "unspecified"))
    )
    (net (code "193") (name "unconnected-(U8-Z1-Pad99)") (class "Default")
      (node (ref "U8") (pin "99") (pinfunction "Z1_99") (pintype "unspecified"))
    )
    (net (code "194") (name "unconnected-(U8-Z2-Pad100)") (class "Default")
      (node (ref "U8") (pin "100") (pinfunction "Z2_100") (pintype "unspecified"))
    )
    (net (code "195") (name "unconnected-(U8-Z3-Pad101)") (class "Default")
      (node (ref "U8") (pin "101") (pinfunction "Z3_101") (pintype "unspecified"))
    )
    (net (code "196") (name "unconnected-(U8-Z4-Pad102)") (class "Default")
      (node (ref "U8") (pin "102") (pinfunction "Z4_102") (pintype "unspecified"))
    )
  )
)
